# 10_Wifi.net
KiCad netlist of a schematic drawn in Altium Designer
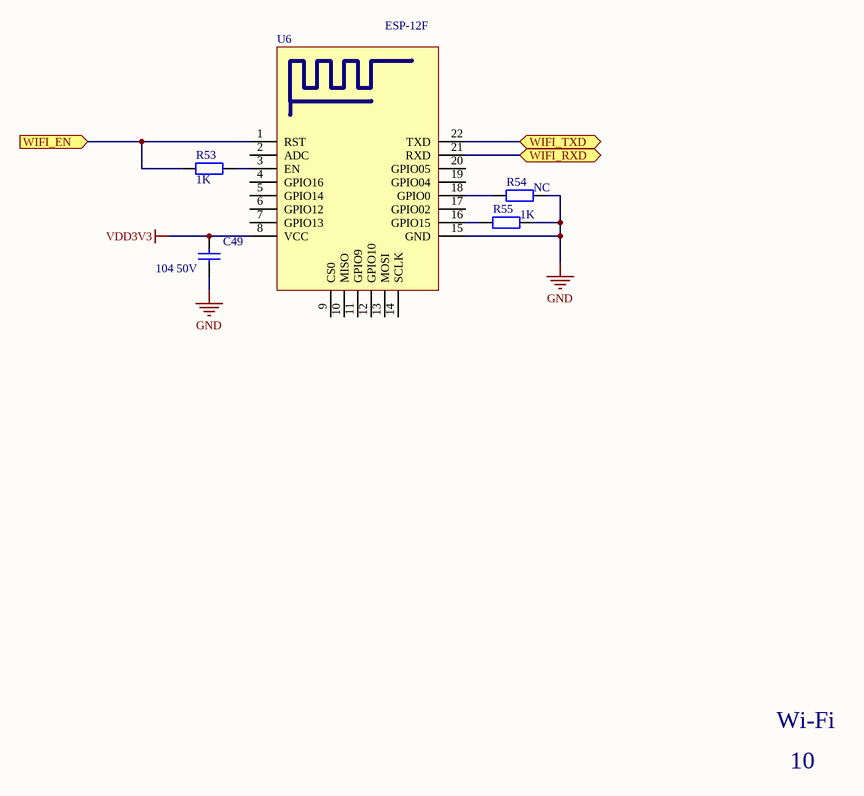
[diagram p0: 10_Wifi.SchDoc]

(export (version "E")
  (design (tool "Eeschema 10.0.6"))
  (components
    (comp (ref "C49")
      (value "104 50V")
      (footprint "SMD-0603C")
      (description "贴片电容 20%")
      (libsource (lib "XiaoyI") (part "CAP4"))
    )
    (comp (ref "R53")
      (value "1K")
      (footprint "SMD-0603")
      (description "贴片电阻 5%")
      (libsource (lib "XiaoyI") (part "RES2"))
    )
    (comp (ref "R54")
      (value "NC")
      (footprint "SMD-0603")
      (description "贴片电阻 5%")
      (libsource (lib "") (part "RES2_1"))
    )
    (comp (ref "R55")
      (value "1K")
      (footprint "SMD-0603")
      (description "贴片电阻 5%")
      (libsource (lib "XiaoyI") (part "RES2"))
    )
    (comp (ref "U6")
      (value "ESP-12F")
      (footprint "ESP-12F")
      (libsource (lib "YS-F1Pro开发板主板") (part "ESP8266"))
    )
  )
  (nets
    (net (code "1") (name "/WIFI_EN") (class "Default")
      (node (ref "R53") (pin "1") (pinfunction "1_1") (pintype "passive"))
      (node (ref "U6") (pin "1") (pinfunction "RST_1") (pintype "passive"))
    )
    (net (code "2") (name "/WIFI_RXD") (class "Default")
      (node (ref "U6") (pin "21") (pinfunction "RXD_21") (pintype "passive"))
    )
    (net (code "3") (name "/WIFI_TXD") (class "Default")
      (node (ref "U6") (pin "22") (pinfunction "TXD_22") (pintype "passive"))
    )
    (net (code "4") (name "GND") (class "Default")
      (node (ref "C49") (pin "1") (pinfunction "1_1") (pintype "passive"))
      (node (ref "R54") (pin "1") (pinfunction "1_1") (pintype "passive"))
      (node (ref "R55") (pin "2") (pinfunction "2_2") (pintype "passive"))
      (node (ref "U6") (pin "15") (pinfunction "GND_15") (pintype "passive"))
    )
    (net (code "5") (name "Net-(U6-EN)") (class "Default")
      (node (ref "R53") (pin "2") (pinfunction "2_2") (pintype "passive"))
      (node (ref "U6") (pin "3") (pinfunction "EN_3") (pintype "passive"))
    )
    (net (code "6") (name "Net-(U6-GPIO0)") (class "Default")
      (node (ref "R54") (pin "2") (pinfunction "2_2") (pintype "passive"))
      (node (ref "U6") (pin "18") (pinfunction "GPIO0_18") (pintype "passive"))
    )
    (net (code "7") (name "Net-(U6-GPIO15)") (class "Default")
      (node (ref "R55") (pin "1") (pinfunction "1_1") (pintype "passive"))
      (node (ref "U6") (pin "16") (pinfunction "GPIO15_16") (pintype "passive"))
    )
    (net (code "8") (name "VDD3V3") (class "Default")
      (node (ref "C49") (pin "2") (pinfunction "2_2") (pintype "passive"))
      (node (ref "U6") (pin "8") (pinfunction "VCC_8") (pintype "passive"))
    )
    (net (code "9") (name "unconnected-(U6-ADC-Pad2)") (class "Default")
      (node (ref "U6") (pin "2") (pinfunction "ADC_2") (pintype "passive"))
    )
    (net (code "10") (name "unconnected-(U6-CS0-Pad9)") (class "Default")
      (node (ref "U6") (pin "9") (pinfunction "CS0_9") (pintype "passive"))
    )
    (net (code "11") (name "unconnected-(U6-GPIO02-Pad17)") (class "Default")
      (node (ref "U6") (pin "17") (pinfunction "GPIO02_17") (pintype "passive"))
    )
    (net (code "12") (name "unconnected-(U6-GPIO04-Pad19)") (class "Default")
      (node (ref "U6") (pin "19") (pinfunction "GPIO04_19") (pintype "passive"))
    )
    (net (code "13") (name "unconnected-(U6-GPIO05-Pad20)") (class "Default")
      (node (ref "U6") (pin "20") (pinfunction "GPIO05_20") (pintype "passive"))
    )
    (net (code "14") (name "unconnected-(U6-GPIO9-Pad11)") (class "Default")
      (node (ref "U6") (pin "11") (pinfunction "GPIO9_11") (pintype "passive"))
    )
    (net (code "15") (name "unconnected-(U6-GPIO10-Pad12)") (class "Default")
      (node (ref "U6") (pin "12") (pinfunction "GPIO10_12") (pintype "passive"))
    )
    (net (code "16") (name "unconnected-(U6-GPIO12-Pad6)") (class "Default")
      (node (ref "U6") (pin "6") (pinfunction "GPIO12_6") (pintype "passive"))
    )
    (net (code "17") (name "unconnected-(U6-GPIO13-Pad7)") (class "Default")
      (node (ref "U6") (pin "7") (pinfunction "GPIO13_7") (pintype "passive"))
    )
    (net (code "18") (name "unconnected-(U6-GPIO14-Pad5)") (class "Default")
      (node (ref "U6") (pin "5") (pinfunction "GPIO14_5") (pintype "passive"))
    )
    (net (code "19") (name "unconnected-(U6-GPIO16-Pad4)") (class "Default")
      (node (ref "U6") (pin "4") (pinfunction "GPIO16_4") (pintype "passive"))
    )
    (net (code "20") (name "unconnected-(U6-MISO-Pad10)") (class "Default")
      (node (ref "U6") (pin "10") (pinfunction "MISO_10") (pintype "passive"))
    )
    (net (code "21") (name "unconnected-(U6-MOSI-Pad13)") (class "Default")
      (node (ref "U6") (pin "13") (pinfunction "MOSI_13") (pintype "passive"))
    )
    (net (code "22") (name "unconnected-(U6-SCLK-Pad14)") (class "Default")
      (node (ref "U6") (pin "14") (pinfunction "SCLK_14") (pintype "passive"))
    )
  )
)
